# lineterm.net
KiCad netlist of a schematic drawn in EAGLE
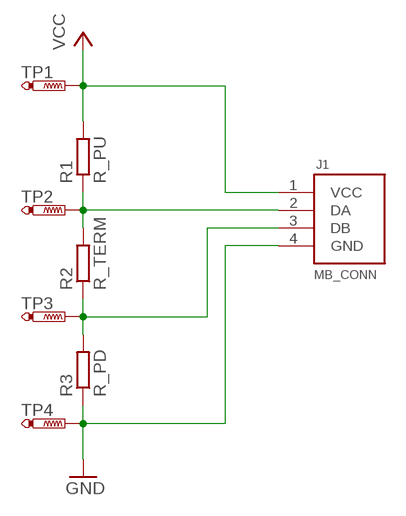
[diagram p0: schematic, sheet 1]

(export (version "E")
  (design (tool "Eeschema 10.0.6"))
  (components
    (comp (ref "J1")
      (value "MB_CONN")
      (footprint "eagle-import:PTSM0,5_4-HH-2,5-THR")
      (libsource (lib "eagle-import") (part "MB_CONN"))
    )
    (comp (ref "R1")
      (value "R_PU")
      (footprint "eagle-import:0207_12")
      (libsource (lib "eagle-import") (part "R-EU_0207/12"))
    )
    (comp (ref "R2")
      (value "R_TERM")
      (footprint "eagle-import:0207_12")
      (libsource (lib "eagle-import") (part "R-EU_0207/12"))
    )
    (comp (ref "R3")
      (value "R_PD")
      (footprint "eagle-import:0207_12")
      (libsource (lib "eagle-import") (part "R-EU_0207/12"))
    )
    (comp (ref "TP1")
      (value "PTR1TP15R")
      (footprint "eagle-import:TP15R")
      (libsource (lib "eagle-import") (part "PTR1TP15R"))
    )
    (comp (ref "TP2")
      (value "PTR1TP15R")
      (footprint "eagle-import:TP15R")
      (libsource (lib "eagle-import") (part "PTR1TP15R"))
    )
    (comp (ref "TP3")
      (value "PTR1TP15R")
      (footprint "eagle-import:TP15R")
      (libsource (lib "eagle-import") (part "PTR1TP15R"))
    )
    (comp (ref "TP4")
      (value "PTR1TP15R")
      (footprint "eagle-import:TP15R")
      (libsource (lib "eagle-import") (part "PTR1TP15R"))
    )
  )
  (nets
    (net (code "1") (name "GND") (class "Default")
      (node (ref "J1") (pin "4") (pinfunction "GND_4") (pintype "passive"))
      (node (ref "R3") (pin "1") (pinfunction "1_1") (pintype "passive"))
      (node (ref "TP4") (pin "TP") (pinfunction "TP_TP") (pintype "input"))
    )
    (net (code "2") (name "Net-(J1-DA)") (class "Default")
      (node (ref "J1") (pin "2") (pinfunction "DA_2") (pintype "bidirectional"))
      (node (ref "R1") (pin "1") (pinfunction "1_1") (pintype "passive"))
      (node (ref "R2") (pin "2") (pinfunction "2_2") (pintype "passive"))
      (node (ref "TP2") (pin "TP") (pinfunction "TP_TP") (pintype "input"))
    )
    (net (code "3") (name "Net-(J1-DB)") (class "Default")
      (node (ref "J1") (pin "3") (pinfunction "DB_3") (pintype "bidirectional"))
      (node (ref "R2") (pin "1") (pinfunction "1_1") (pintype "passive"))
      (node (ref "R3") (pin "2") (pinfunction "2_2") (pintype "passive"))
      (node (ref "TP3") (pin "TP") (pinfunction "TP_TP") (pintype "input"))
    )
    (net (code "4") (name "VCC") (class "Default")
      (node (ref "J1") (pin "1") (pinfunction "VCC_1") (pintype "power_in"))
      (node (ref "R1") (pin "2") (pinfunction "2_2") (pintype "passive"))
      (node (ref "TP1") (pin "TP") (pinfunction "TP_TP") (pintype "input"))
    )
  )
)
